# ethernet-wing-v1_00.net
KiCad netlist of a schematic drawn in EAGLE
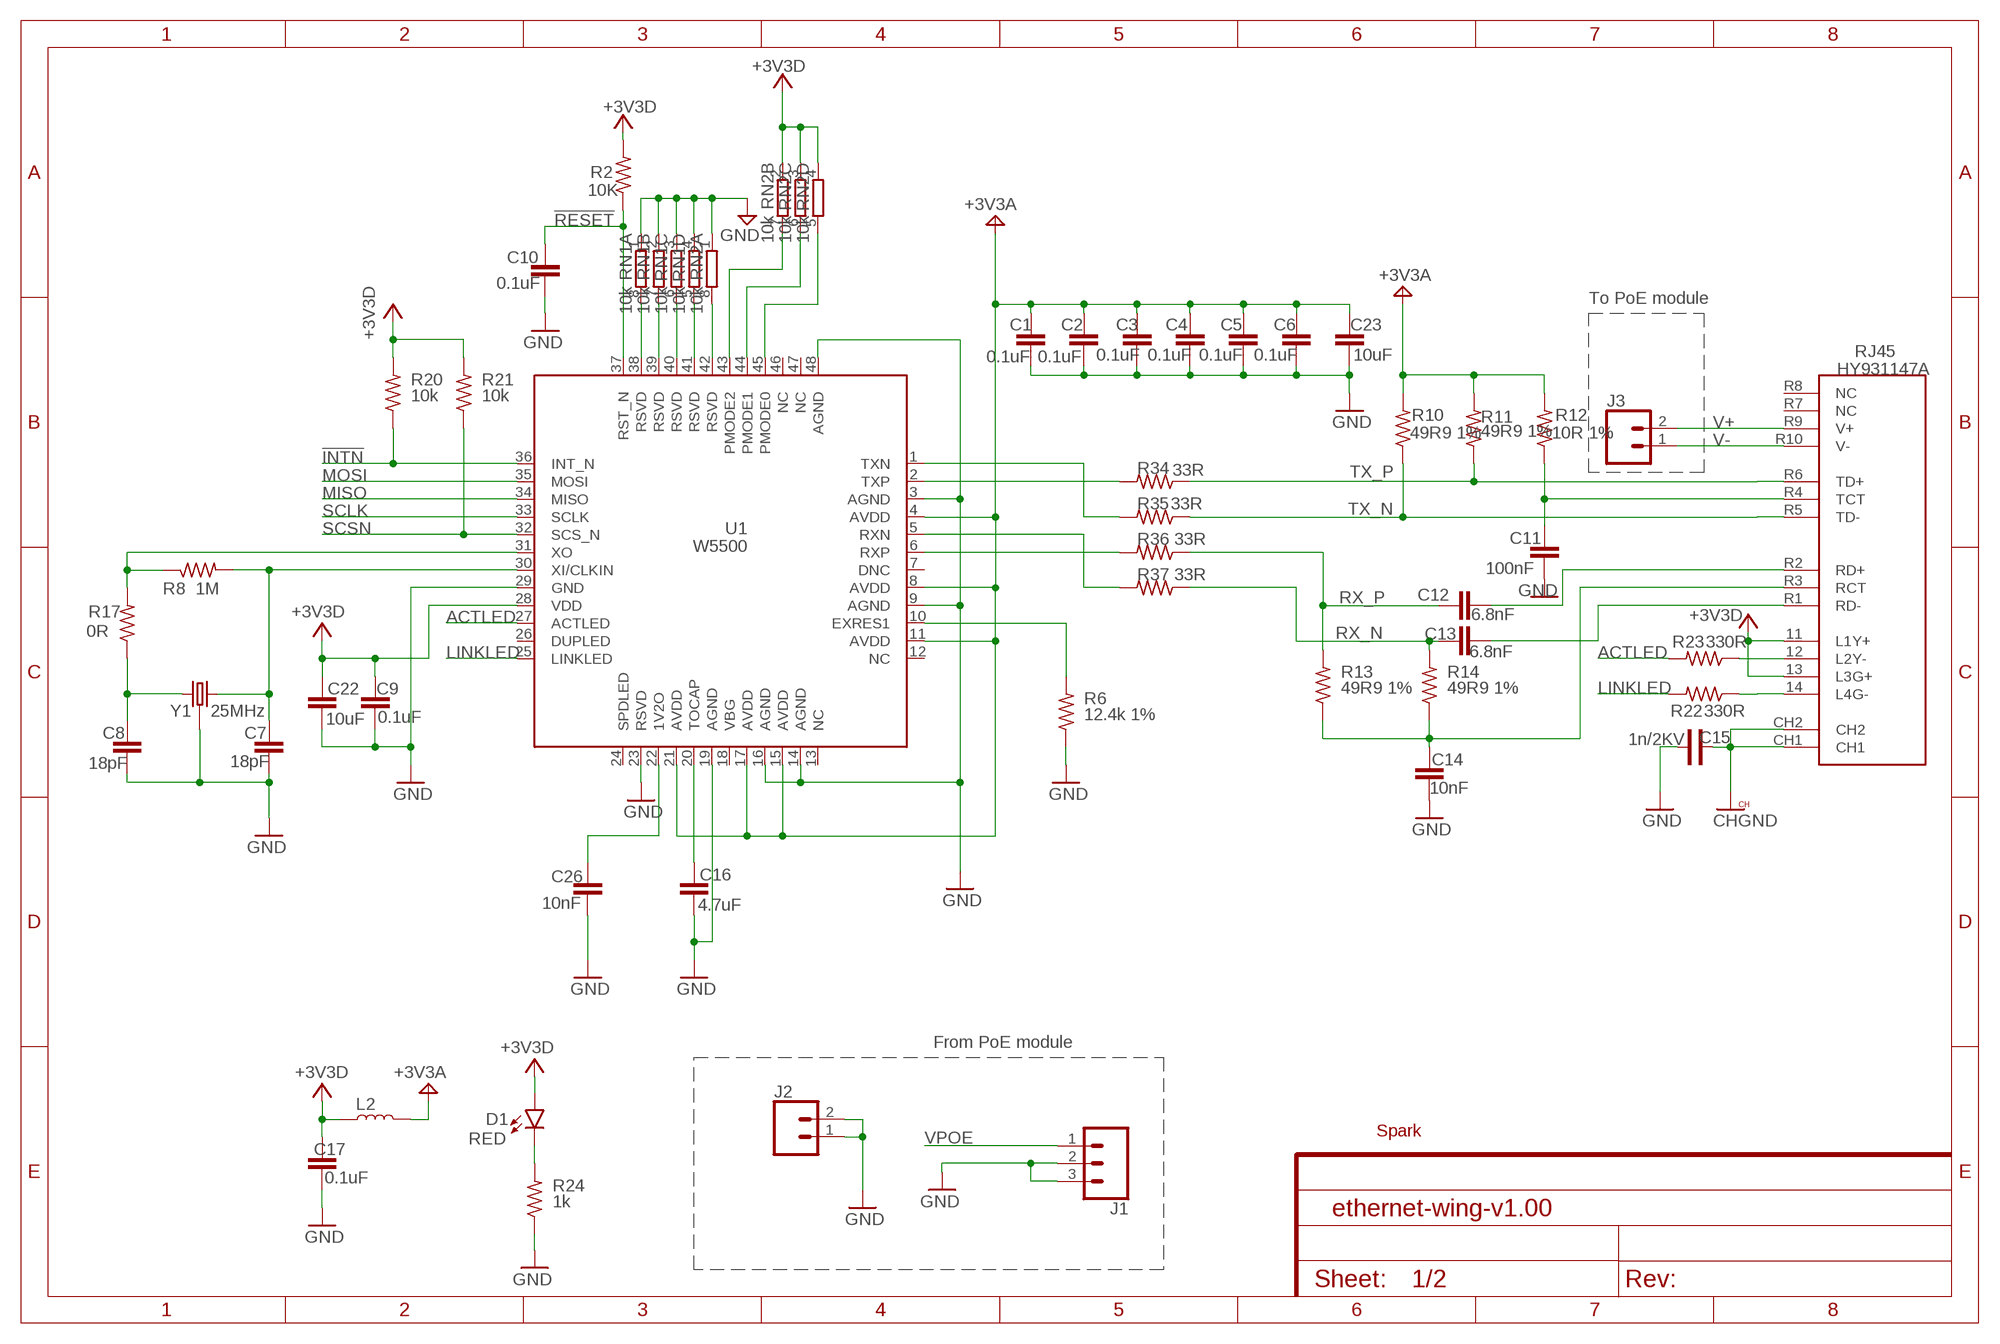
[diagram p0: schematic, sheet 1]
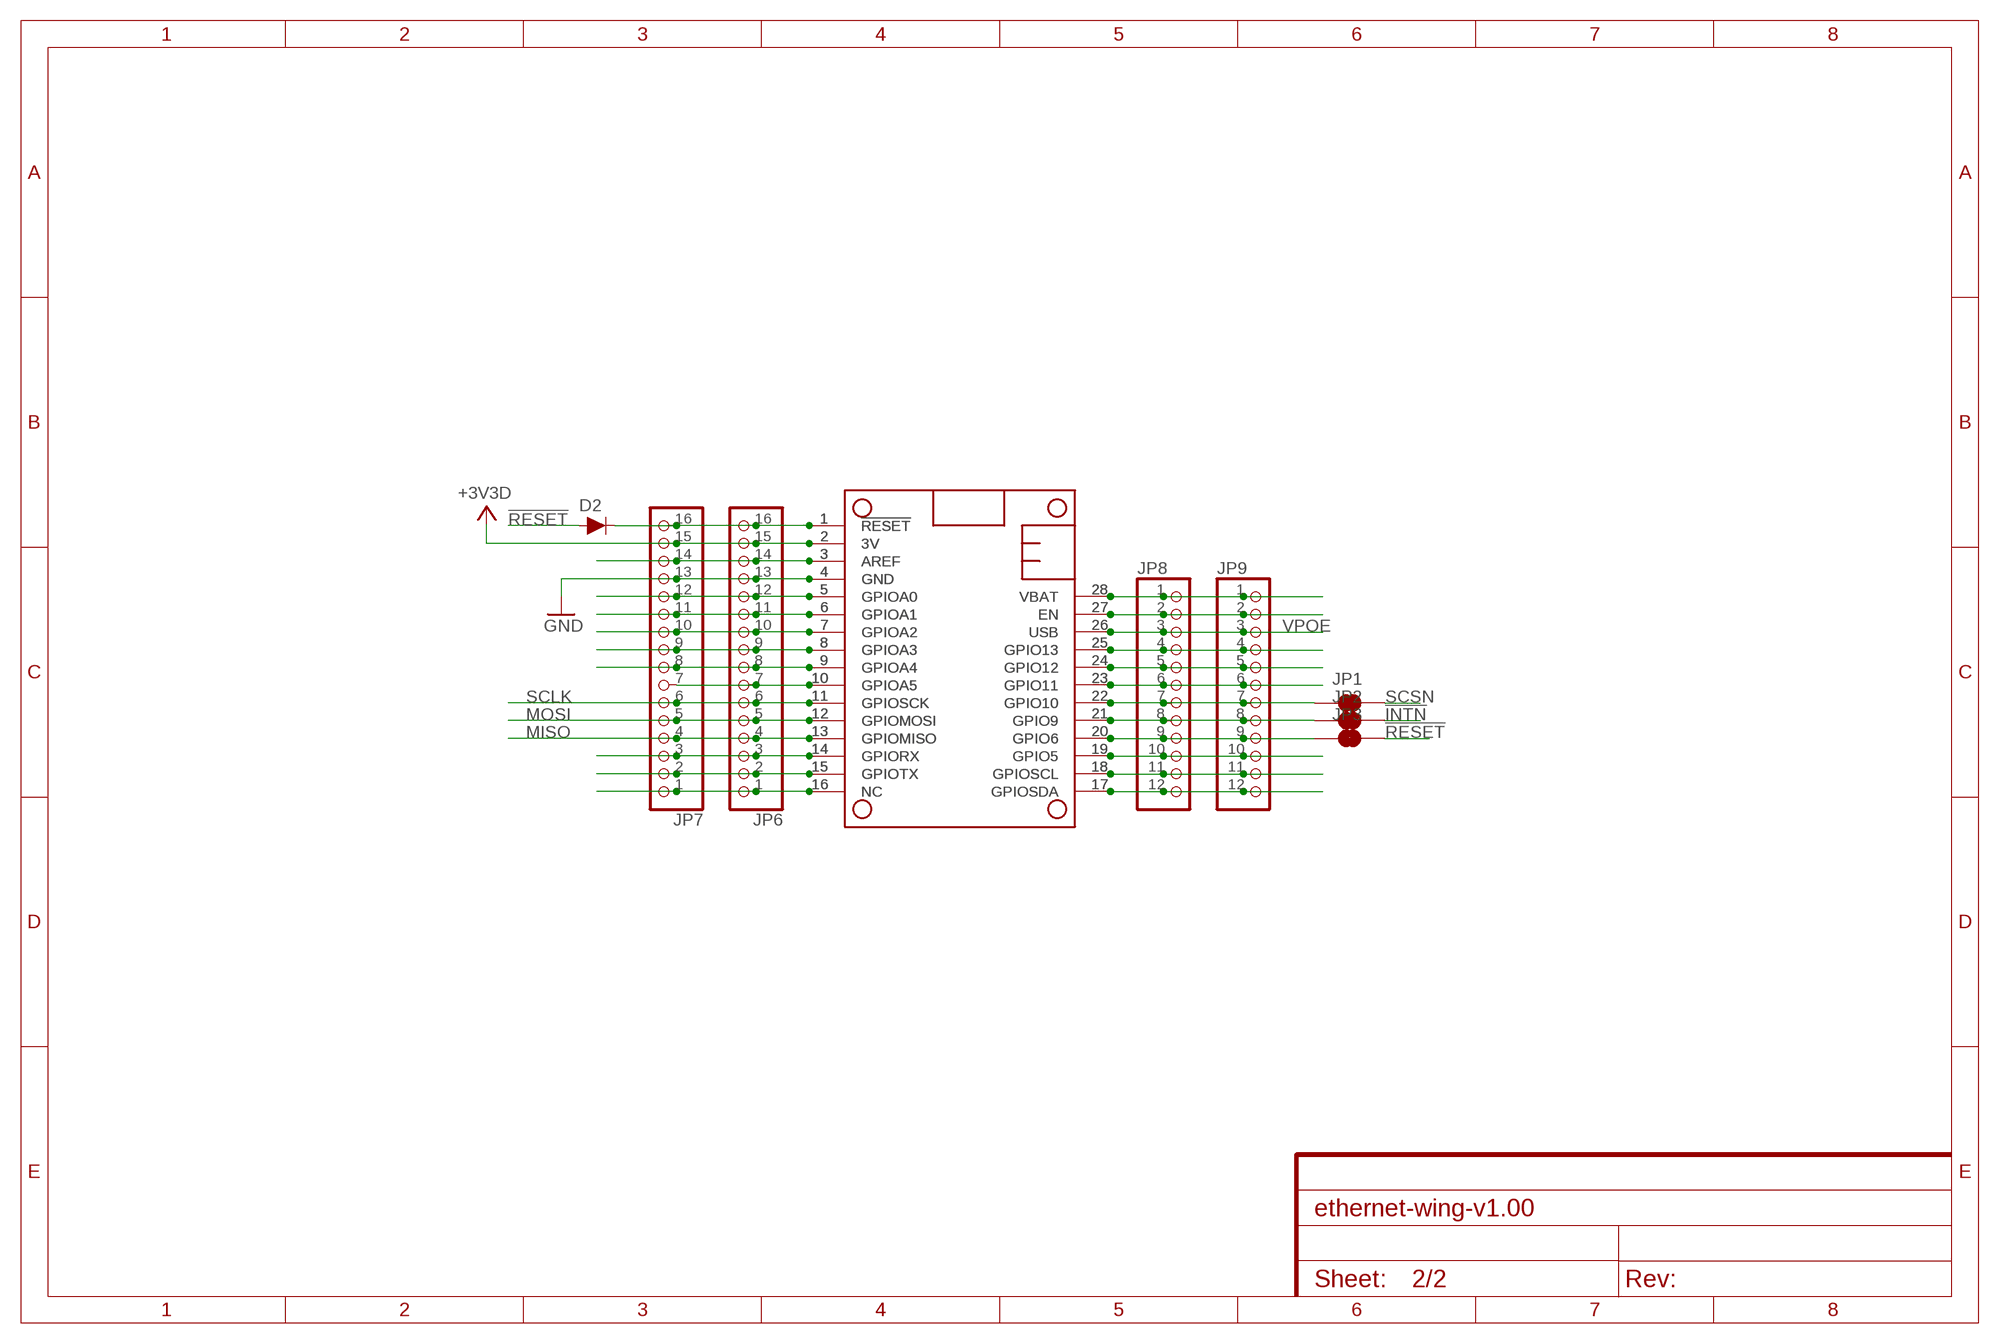
[diagram p1: schematic, sheet 2]

(export (version "E")
  (design (tool "Eeschema 10.0.6"))
  (components
    (comp (ref "C1")
      (value "0.1uF")
      (footprint "eagle-import:C0402_B")
      (libsource (lib "eagle-import") (part "CAP_1"))
    )
    (comp (ref "C2")
      (value "0.1uF")
      (footprint "eagle-import:C0402_B")
      (libsource (lib "eagle-import") (part "CAP_1"))
    )
    (comp (ref "C3")
      (value "0.1uF")
      (footprint "eagle-import:C0402_B")
      (libsource (lib "eagle-import") (part "CAP_1"))
    )
    (comp (ref "C4")
      (value "0.1uF")
      (footprint "eagle-import:C0402_B")
      (libsource (lib "eagle-import") (part "CAP_1"))
    )
    (comp (ref "C5")
      (value "0.1uF")
      (footprint "eagle-import:C0402_B")
      (libsource (lib "eagle-import") (part "CAP_1"))
    )
    (comp (ref "C6")
      (value "0.1uF")
      (footprint "eagle-import:C0402_B")
      (libsource (lib "eagle-import") (part "CAP_1"))
    )
    (comp (ref "C7")
      (value "18pF")
      (footprint "eagle-import:C0402_B")
      (libsource (lib "eagle-import") (part "CAP_1"))
    )
    (comp (ref "C8")
      (value "18pF")
      (footprint "eagle-import:C0402_B")
      (libsource (lib "eagle-import") (part "CAP_1"))
    )
    (comp (ref "C9")
      (value "0.1uF")
      (footprint "eagle-import:C0402_B")
      (libsource (lib "eagle-import") (part "CAP_1"))
    )
    (comp (ref "C10")
      (value "0.1uF")
      (footprint "eagle-import:C0402_B")
      (libsource (lib "eagle-import") (part "CAP_1"))
    )
    (comp (ref "C11")
      (value "100nF")
      (footprint "eagle-import:C0402_B")
      (libsource (lib "eagle-import") (part "CAP_1"))
    )
    (comp (ref "C12")
      (value "6.8nF")
      (footprint "eagle-import:C0402_B")
      (libsource (lib "eagle-import") (part "CAP_1"))
    )
    (comp (ref "C13")
      (value "6.8nF")
      (footprint "eagle-import:C0402_B")
      (libsource (lib "eagle-import") (part "CAP_1"))
    )
    (comp (ref "C14")
      (value "10nF")
      (footprint "eagle-import:C0402_B")
      (libsource (lib "eagle-import") (part "CAP_1"))
    )
    (comp (ref "C15")
      (value "1n/2KV")
      (footprint "eagle-import:C-1808")
      (libsource (lib "eagle-import") (part "C-1808"))
    )
    (comp (ref "C16")
      (value "4.7uF")
      (footprint "eagle-import:0603")
      (libsource (lib "eagle-import") (part "0.18UF-0603-10V-10%"))
    )
    (comp (ref "C17")
      (value "0.1uF")
      (footprint "eagle-import:C0402_B")
      (libsource (lib "eagle-import") (part "CAP_1"))
    )
    (comp (ref "C22")
      (value "10uF")
      (footprint "eagle-import:0603")
      (libsource (lib "eagle-import") (part "0.18UF-0603-10V-10%"))
    )
    (comp (ref "C23")
      (value "10uF")
      (footprint "eagle-import:0603")
      (libsource (lib "eagle-import") (part "0.18UF-0603-10V-10%"))
    )
    (comp (ref "C26")
      (value "10nF")
      (footprint "eagle-import:C0402_B")
      (libsource (lib "eagle-import") (part "CAP_1"))
    )
    (comp (ref "D1")
      (value "RED")
      (footprint "eagle-import:LED-0603")
      (libsource (lib "eagle-import") (part "LED-RED0603"))
    )
    (comp (ref "J1")
      (value "CONN_03")
      (footprint "eagle-import:1X03")
      (libsource (lib "eagle-import") (part "CONN_03"))
    )
    (comp (ref "J2")
      (value "CONN_02")
      (footprint "eagle-import:1X02")
      (libsource (lib "eagle-import") (part "CONN_02"))
    )
    (comp (ref "J3")
      (value "CONN_02")
      (footprint "eagle-import:1X02")
      (libsource (lib "eagle-import") (part "CONN_02"))
    )
    (comp (ref "L2")
      (value "INDUCTOR-0805-3.3UH")
      (footprint "eagle-import:0805")
      (libsource (lib "eagle-import") (part "INDUCTOR-0805-3.3UH"))
    )
    (comp (ref "R2")
      (value "10K")
      (footprint "eagle-import:R0402_B")
      (libsource (lib "eagle-import") (part "R-US_"))
    )
    (comp (ref "R6")
      (value "12.4k 1%")
      (footprint "eagle-import:R0402_B")
      (libsource (lib "eagle-import") (part "R-US_"))
    )
    (comp (ref "R8")
      (value "1M")
      (footprint "eagle-import:R0402_B")
      (libsource (lib "eagle-import") (part "R-US_"))
    )
    (comp (ref "R10")
      (value "49R9 1%")
      (footprint "eagle-import:R0402_B")
      (libsource (lib "eagle-import") (part "R-US_"))
    )
    (comp (ref "R11")
      (value "49R9 1%")
      (footprint "eagle-import:R0402_B")
      (libsource (lib "eagle-import") (part "R-US_"))
    )
    (comp (ref "R12")
      (value "10R 1%")
      (footprint "eagle-import:R0402_B")
      (libsource (lib "eagle-import") (part "R-US_"))
    )
    (comp (ref "R13")
      (value "49R9 1%")
      (footprint "eagle-import:R0402_B")
      (libsource (lib "eagle-import") (part "R-US_"))
    )
    (comp (ref "R14")
      (value "49R9 1%")
      (footprint "eagle-import:R0402_B")
      (libsource (lib "eagle-import") (part "R-US_"))
    )
    (comp (ref "R17")
      (value "0R")
      (footprint "eagle-import:R0402_B")
      (libsource (lib "eagle-import") (part "R-US_"))
    )
    (comp (ref "R20")
      (value "10k")
      (footprint "eagle-import:R0402_B")
      (libsource (lib "eagle-import") (part "R-US_"))
    )
    (comp (ref "R21")
      (value "10k")
      (footprint "eagle-import:R0402_B")
      (libsource (lib "eagle-import") (part "R-US_"))
    )
    (comp (ref "R22")
      (value "330R")
      (footprint "eagle-import:R0402_B")
      (libsource (lib "eagle-import") (part "R-US_"))
    )
    (comp (ref "R23")
      (value "330R")
      (footprint "eagle-import:R0402_B")
      (libsource (lib "eagle-import") (part "R-US_"))
    )
    (comp (ref "R24")
      (value "1k")
      (footprint "eagle-import:R0402_B")
      (libsource (lib "eagle-import") (part "R-US_"))
    )
    (comp (ref "R34")
      (value "33R")
      (footprint "eagle-import:R0402_B")
      (libsource (lib "eagle-import") (part "R-US_"))
    )
    (comp (ref "R35")
      (value "33R")
      (footprint "eagle-import:R0402_B")
      (libsource (lib "eagle-import") (part "R-US_"))
    )
    (comp (ref "R36")
      (value "33R")
      (footprint "eagle-import:R0402_B")
      (libsource (lib "eagle-import") (part "R-US_"))
    )
    (comp (ref "R37")
      (value "33R")
      (footprint "eagle-import:R0402_B")
      (libsource (lib "eagle-import") (part "R-US_"))
    )
    (comp (ref "RJ45")
      (value "HY931147A")
      (footprint "eagle-import:ARDUINO-ETHERNET-SHIELD2-V2_CONNETTORI_POE-RJ45")
      (libsource (lib "eagle-import") (part "ARDUINO-ETHERNET-SHIELD2-V2_POE_RJ45"))
    )
    (comp (ref "RN1")
      (value "10k")
      (footprint "eagle-import:4X0402ARV341")
      (libsource (lib "eagle-import") (part "4R-N0402ARV341"))
    )
    (comp (ref "RN2")
      (value "10k")
      (footprint "eagle-import:4X0402ARV341")
      (libsource (lib "eagle-import") (part "4R-N0402ARV341"))
    )
    (comp (ref "U$2")
      (value "SPARK_LOGO2")
      (footprint "eagle-import:SPARK_LOGO2")
      (libsource (lib "eagle-import") (part "SPARK_LOGO2"))
    )
    (comp (ref "U1")
      (value "W5500")
      (footprint "eagle-import:W5500")
      (libsource (lib "eagle-import") (part "W5500"))
    )
    (comp (ref "Y1")
      (value "25MHz")
      (footprint "eagle-import:CRYSTAL-SMD-3.2X2.5MM")
      (libsource (lib "eagle-import") (part "CRYSTAL-GROUNDEDSMD-3.2X2.5"))
    )
    (comp (ref "D2")
      (value "DIODE-BAS16J")
      (footprint "eagle-import:SOD-323")
      (libsource (lib "eagle-import") (part "DIODE-BAS16J"))
    )
    (comp (ref "JP1")
      (value "JUMPER-SMT_2_NC_TRACE_NO-SILK")
      (footprint "eagle-import:SMT-JUMPER_2_NC_TRACE_NO-SILK")
      (libsource (lib "eagle-import") (part "JUMPER-SMT_2_NC_TRACE_NO-SILK"))
    )
    (comp (ref "JP2")
      (value "JUMPER-SMT_2_NC_TRACE_NO-SILK")
      (footprint "eagle-import:SMT-JUMPER_2_NC_TRACE_NO-SILK")
      (libsource (lib "eagle-import") (part "JUMPER-SMT_2_NC_TRACE_NO-SILK"))
    )
    (comp (ref "JP3")
      (value "JUMPER-SMT_2_NC_TRACE_NO-SILK")
      (footprint "eagle-import:SMT-JUMPER_2_NC_TRACE_NO-SILK")
      (libsource (lib "eagle-import") (part "JUMPER-SMT_2_NC_TRACE_NO-SILK"))
    )
    (comp (ref "JP6")
      (value "MICROBUILDER_HEADER-1X16_76MIL")
      (footprint "eagle-import:MICROBUILDER_1X16_ROUND_76MIL")
      (libsource (lib "eagle-import") (part "MICROBUILDER_HEADER-1X16_76MIL"))
    )
    (comp (ref "JP7")
      (value "MICROBUILDER_HEADER-1X16_76MIL")
      (footprint "eagle-import:MICROBUILDER_1X16_ROUND_76MIL")
      (libsource (lib "eagle-import") (part "MICROBUILDER_HEADER-1X16_76MIL"))
    )
    (comp (ref "JP8")
      (value "MICROBUILDER_HEADER-1X1276MIL")
      (footprint "eagle-import:MICROBUILDER_1X12_ROUND_76MIL")
      (libsource (lib "eagle-import") (part "MICROBUILDER_HEADER-1X1276MIL"))
    )
    (comp (ref "JP9")
      (value "MICROBUILDER_HEADER-1X1276MIL")
      (footprint "eagle-import:MICROBUILDER_1X12_ROUND_76MIL")
      (libsource (lib "eagle-import") (part "MICROBUILDER_HEADER-1X1276MIL"))
    )
    (comp (ref "MS1")
      (value "MICROBUILDER_FEATHERWING_NODIM")
      (footprint "eagle-import:MICROBUILDER_FEATHERWING_DIM")
      (libsource (lib "eagle-import") (part "MICROBUILDER_FEATHERWING_NODIM"))
    )
    (comp (ref "MS2")
      (value "MICROBUILDER_FEATHERWING_NODIM")
      (footprint "eagle-import:MICROBUILDER_FEATHERWING_DIM")
      (libsource (lib "eagle-import") (part "MICROBUILDER_FEATHERWING_NODIM"))
    )
  )
  (nets
    (net (code "1") (name "+3V3") (class "Default")
      (node (ref "C17") (pin "2") (pinfunction "P$2_2") (pintype "passive"))
      (node (ref "C22") (pin "1") (pinfunction "1_1") (pintype "passive"))
      (node (ref "C9") (pin "2") (pinfunction "P$2_2") (pintype "passive"))
      (node (ref "D1") (pin "A") (pinfunction "A_A") (pintype "passive"))
      (node (ref "JP6") (pin "15") (pinfunction "15_15") (pintype "passive"))
      (node (ref "JP7") (pin "15") (pinfunction "15_15") (pintype "passive"))
      (node (ref "L2") (pin "1") (pinfunction "1_1") (pintype "passive"))
      (node (ref "MS1") (pin "2") (pinfunction "3V_2") (pintype "power_in"))
      (node (ref "MS2") (pin "2") (pinfunction "3V_2") (pintype "power_in"))
      (node (ref "R2") (pin "2") (pinfunction "2_2") (pintype "passive"))
      (node (ref "R20") (pin "2") (pinfunction "2_2") (pintype "passive"))
      (node (ref "R21") (pin "2") (pinfunction "2_2") (pintype "passive"))
      (node (ref "RJ45") (pin "11") (pinfunction "L1Y+_11") (pintype "bidirectional"))
      (node (ref "RJ45") (pin "13") (pinfunction "L3G+_13") (pintype "bidirectional"))
      (node (ref "RN2") (pin "2") (pinfunction "1_2") (pintype "passive"))
      (node (ref "RN2") (pin "3") (pinfunction "1_3") (pintype "passive"))
      (node (ref "RN2") (pin "4") (pinfunction "1_4") (pintype "passive"))
      (node (ref "U1") (pin "28") (pinfunction "VDD_28") (pintype "passive"))
    )
    (net (code "2") (name "+3V3A") (class "Default")
      (node (ref "C1") (pin "2") (pinfunction "P$2_2") (pintype "passive"))
      (node (ref "C2") (pin "2") (pinfunction "P$2_2") (pintype "passive"))
      (node (ref "C23") (pin "1") (pinfunction "1_1") (pintype "passive"))
      (node (ref "C3") (pin "2") (pinfunction "P$2_2") (pintype "passive"))
      (node (ref "C4") (pin "2") (pinfunction "P$2_2") (pintype "passive"))
      (node (ref "C5") (pin "2") (pinfunction "P$2_2") (pintype "passive"))
      (node (ref "C6") (pin "2") (pinfunction "P$2_2") (pintype "passive"))
      (node (ref "L2") (pin "2") (pinfunction "2_2") (pintype "passive"))
      (node (ref "R10") (pin "2") (pinfunction "2_2") (pintype "passive"))
      (node (ref "R11") (pin "2") (pinfunction "2_2") (pintype "passive"))
      (node (ref "R12") (pin "2") (pinfunction "2_2") (pintype "passive"))
      (node (ref "U1") (pin "11") (pinfunction "AVDD_11") (pintype "passive"))
      (node (ref "U1") (pin "15") (pinfunction "AVDD_15") (pintype "passive"))
      (node (ref "U1") (pin "17") (pinfunction "AVDD_17") (pintype "passive"))
      (node (ref "U1") (pin "21") (pinfunction "AVDD_21") (pintype "passive"))
      (node (ref "U1") (pin "4") (pinfunction "AVDD_4") (pintype "passive"))
      (node (ref "U1") (pin "8") (pinfunction "AVDD_8") (pintype "passive"))
    )
    (net (code "3") (name "ACTLED") (class "Default")
      (node (ref "R23") (pin "2") (pinfunction "2_2") (pintype "passive"))
      (node (ref "U1") (pin "27") (pinfunction "ACTLED_27") (pintype "passive"))
    )
    (net (code "4") (name "CHGND") (class "Default")
      (node (ref "C15") (pin "P$1") (pinfunction "P$1_P$1") (pintype "passive"))
      (node (ref "RJ45") (pin "CH1") (pinfunction "CH1_CH1") (pintype "bidirectional"))
      (node (ref "RJ45") (pin "CH2") (pinfunction "CH2_CH2") (pintype "bidirectional"))
    )
    (net (code "5") (name "GND") (class "Default")
      (node (ref "C1") (pin "1") (pinfunction "P$1_1") (pintype "passive"))
      (node (ref "C10") (pin "1") (pinfunction "P$1_1") (pintype "passive"))
      (node (ref "C11") (pin "1") (pinfunction "P$1_1") (pintype "passive"))
      (node (ref "C14") (pin "1") (pinfunction "P$1_1") (pintype "passive"))
      (node (ref "C15") (pin "P$2") (pinfunction "P$2_P$2") (pintype "passive"))
      (node (ref "C16") (pin "2") (pinfunction "2_2") (pintype "passive"))
      (node (ref "C17") (pin "1") (pinfunction "P$1_1") (pintype "passive"))
      (node (ref "C2") (pin "1") (pinfunction "P$1_1") (pintype "passive"))
      (node (ref "C22") (pin "2") (pinfunction "2_2") (pintype "passive"))
      (node (ref "C23") (pin "2") (pinfunction "2_2") (pintype "passive"))
      (node (ref "C26") (pin "1") (pinfunction "P$1_1") (pintype "passive"))
      (node (ref "C3") (pin "1") (pinfunction "P$1_1") (pintype "passive"))
      (node (ref "C4") (pin "1") (pinfunction "P$1_1") (pintype "passive"))
      (node (ref "C5") (pin "1") (pinfunction "P$1_1") (pintype "passive"))
      (node (ref "C6") (pin "1") (pinfunction "P$1_1") (pintype "passive"))
      (node (ref "C7") (pin "1") (pinfunction "P$1_1") (pintype "passive"))
      (node (ref "C8") (pin "1") (pinfunction "P$1_1") (pintype "passive"))
      (node (ref "C9") (pin "1") (pinfunction "P$1_1") (pintype "passive"))
      (node (ref "J1") (pin "2") (pinfunction "2_2") (pintype "passive"))
      (node (ref "J1") (pin "3") (pinfunction "3_3") (pintype "passive"))
      (node (ref "J2") (pin "1") (pinfunction "1_1") (pintype "passive"))
      (node (ref "J2") (pin "2") (pinfunction "2_2") (pintype "passive"))
      (node (ref "JP6") (pin "13") (pinfunction "13_13") (pintype "passive"))
      (node (ref "JP7") (pin "13") (pinfunction "13_13") (pintype "passive"))
      (node (ref "MS1") (pin "4") (pinfunction "GND_4") (pintype "power_in"))
      (node (ref "MS2") (pin "4") (pinfunction "GND_4") (pintype "power_in"))
      (node (ref "R24") (pin "1") (pinfunction "1_1") (pintype "passive"))
      (node (ref "R6") (pin "1") (pinfunction "1_1") (pintype "passive"))
      (node (ref "RN1") (pin "1") (pinfunction "1_1") (pintype "passive"))
      (node (ref "RN1") (pin "2") (pinfunction "1_2") (pintype "passive"))
      (node (ref "RN1") (pin "3") (pinfunction "1_3") (pintype "passive"))
      (node (ref "RN1") (pin "4") (pinfunction "1_4") (pintype "passive"))
      (node (ref "RN2") (pin "1") (pinfunction "1_1") (pintype "passive"))
      (node (ref "U1") (pin "14") (pinfunction "AGND_14") (pintype "passive"))
      (node (ref "U1") (pin "16") (pinfunction "AGND_16") (pintype "passive"))
      (node (ref "U1") (pin "19") (pinfunction "AGND_19") (pintype "passive"))
      (node (ref "U1") (pin "23") (pinfunction "RSVD_23") (pintype "passive"))
      (node (ref "U1") (pin "29") (pinfunction "GND_29") (pintype "passive"))
      (node (ref "U1") (pin "3") (pinfunction "AGND_3") (pintype "passive"))
      (node (ref "U1") (pin "48") (pinfunction "AGND_48") (pintype "passive"))
      (node (ref "U1") (pin "9") (pinfunction "AGND_9") (pintype "passive"))
      (node (ref "Y1") (pin "2") (pinfunction "3_2") (pintype "passive"))
      (node (ref "Y1") (pin "4") (pinfunction "3_4") (pintype "passive"))
    )
    (net (code "6") (name "LINKLED") (class "Default")
      (node (ref "R22") (pin "2") (pinfunction "2_2") (pintype "passive"))
      (node (ref "U1") (pin "25") (pinfunction "LINKLED_25") (pintype "passive"))
    )
    (net (code "7") (name "MISO") (class "Default")
      (node (ref "JP6") (pin "4") (pinfunction "4_4") (pintype "passive"))
      (node (ref "JP7") (pin "4") (pinfunction "4_4") (pintype "passive"))
      (node (ref "MS1") (pin "13") (pinfunction "GPIOMISO_13") (pintype "bidirectional"))
      (node (ref "MS2") (pin "13") (pinfunction "GPIOMISO_13") (pintype "bidirectional"))
      (node (ref "U1") (pin "34") (pinfunction "MISO_34") (pintype "passive"))
    )
    (net (code "8") (name "MOSI") (class "Default")
      (node (ref "JP6") (pin "5") (pinfunction "5_5") (pintype "passive"))
      (node (ref "JP7") (pin "5") (pinfunction "5_5") (pintype "passive"))
      (node (ref "MS1") (pin "12") (pinfunction "GPIOMOSI_12") (pintype "bidirectional"))
      (node (ref "MS2") (pin "12") (pinfunction "GPIOMOSI_12") (pintype "bidirectional"))
      (node (ref "U1") (pin "35") (pinfunction "MOSI_35") (pintype "passive"))
    )
    (net (code "9") (name "Net-(C7-P$2)") (class "Default")
      (node (ref "C7") (pin "2") (pinfunction "P$2_2") (pintype "passive"))
      (node (ref "R8") (pin "2") (pinfunction "2_2") (pintype "passive"))
      (node (ref "U1") (pin "30") (pinfunction "XI/CLKIN_30") (pintype "passive"))
      (node (ref "Y1") (pin "3") (pinfunction "2_3") (pintype "passive"))
    )
    (net (code "10") (name "Net-(C8-P$2)") (class "Default")
      (node (ref "C8") (pin "2") (pinfunction "P$2_2") (pintype "passive"))
      (node (ref "R17") (pin "1") (pinfunction "1_1") (pintype "passive"))
      (node (ref "Y1") (pin "1") (pinfunction "1_1") (pintype "passive"))
    )
    (net (code "11") (name "Net-(C11-P$2)") (class "Default")
      (node (ref "C11") (pin "2") (pinfunction "P$2_2") (pintype "passive"))
      (node (ref "R12") (pin "1") (pinfunction "1_1") (pintype "passive"))
      (node (ref "RJ45") (pin "R4") (pinfunction "TCT_R4") (pintype "bidirectional"))
    )
    (net (code "12") (name "Net-(C12-P$2)") (class "Default")
      (node (ref "C12") (pin "2") (pinfunction "P$2_2") (pintype "passive"))
      (node (ref "RJ45") (pin "R2") (pinfunction "RD+_R2") (pintype "bidirectional"))
    )
    (net (code "13") (name "Net-(C13-P$2)") (class "Default")
      (node (ref "C13") (pin "2") (pinfunction "P$2_2") (pintype "passive"))
      (node (ref "RJ45") (pin "R1") (pinfunction "RD-_R1") (pintype "bidirectional"))
    )
    (net (code "14") (name "Net-(C14-P$2)") (class "Default")
      (node (ref "C14") (pin "2") (pinfunction "P$2_2") (pintype "passive"))
      (node (ref "R13") (pin "1") (pinfunction "1_1") (pintype "passive"))
      (node (ref "R14") (pin "1") (pinfunction "1_1") (pintype "passive"))
      (node (ref "RJ45") (pin "R3") (pinfunction "RCT_R3") (pintype "bidirectional"))
    )
    (net (code "15") (name "Net-(C26-P$2)") (class "Default")
      (node (ref "C26") (pin "2") (pinfunction "P$2_2") (pintype "passive"))
      (node (ref "U1") (pin "22") (pinfunction "1V2O_22") (pintype "passive"))
    )
    (net (code "16") (name "Net-(D1-PadC)") (class "Default")
      (node (ref "D1") (pin "C") (pinfunction "C_C") (pintype "passive"))
      (node (ref "R24") (pin "2") (pinfunction "2_2") (pintype "passive"))
    )
    (net (code "17") (name "Net-(MS1-AREF)") (class "Default")
      (node (ref "JP6") (pin "14") (pinfunction "14_14") (pintype "passive"))
      (node (ref "JP7") (pin "14") (pinfunction "14_14") (pintype "passive"))
      (node (ref "MS1") (pin "3") (pinfunction "AREF_3") (pintype "passive"))
      (node (ref "MS2") (pin "3") (pinfunction "AREF_3") (pintype "passive"))
    )
    (net (code "18") (name "Net-(MS1-EN)") (class "Default")
      (node (ref "JP8") (pin "2") (pinfunction "2_2") (pintype "passive"))
      (node (ref "JP9") (pin "2") (pinfunction "2_2") (pintype "passive"))
      (node (ref "MS1") (pin "27") (pinfunction "EN_27") (pintype "passive"))
      (node (ref "MS2") (pin "27") (pinfunction "EN_27") (pintype "passive"))
    )
    (net (code "19") (name "Net-(MS1-GPIO5)") (class "Default")
      (node (ref "JP8") (pin "10") (pinfunction "10_10") (pintype "passive"))
      (node (ref "JP9") (pin "10") (pinfunction "10_10") (pintype "passive"))
      (node (ref "MS1") (pin "19") (pinfunction "GPIO5_19") (pintype "bidirectional"))
      (node (ref "MS2") (pin "19") (pinfunction "GPIO5_19") (pintype "bidirectional"))
    )
    (net (code "20") (name "Net-(MS1-GPIO6)") (class "Default")
      (node (ref "JP3") (pin "1") (pinfunction "1_1") (pintype "passive"))
      (node (ref "JP8") (pin "9") (pinfunction "9_9") (pintype "passive"))
      (node (ref "JP9") (pin "9") (pinfunction "9_9") (pintype "passive"))
      (node (ref "MS1") (pin "20") (pinfunction "GPIO6_20") (pintype "bidirectional"))
      (node (ref "MS2") (pin "20") (pinfunction "GPIO6_20") (pintype "bidirectional"))
    )
    (net (code "21") (name "Net-(MS1-GPIO9)") (class "Default")
      (node (ref "JP2") (pin "1") (pinfunction "1_1") (pintype "passive"))
      (node (ref "JP8") (pin "8") (pinfunction "8_8") (pintype "passive"))
      (node (ref "JP9") (pin "8") (pinfunction "8_8") (pintype "passive"))
      (node (ref "MS1") (pin "21") (pinfunction "GPIO9_21") (pintype "bidirectional"))
      (node (ref "MS2") (pin "21") (pinfunction "GPIO9_21") (pintype "bidirectional"))
    )
    (net (code "22") (name "Net-(MS1-GPIO10)") (class "Default")
      (node (ref "JP1") (pin "1") (pinfunction "1_1") (pintype "passive"))
      (node (ref "JP8") (pin "7") (pinfunction "7_7") (pintype "passive"))
      (node (ref "JP9") (pin "7") (pinfunction "7_7") (pintype "passive"))
      (node (ref "MS1") (pin "22") (pinfunction "GPIO10_22") (pintype "bidirectional"))
      (node (ref "MS2") (pin "22") (pinfunction "GPIO10_22") (pintype "bidirectional"))
    )
    (net (code "23") (name "Net-(MS1-GPIO11)") (class "Default")
      (node (ref "JP8") (pin "6") (pinfunction "6_6") (pintype "passive"))
      (node (ref "JP9") (pin "6") (pinfunction "6_6") (pintype "passive"))
      (node (ref "MS1") (pin "23") (pinfunction "GPIO11_23") (pintype "bidirectional"))
      (node (ref "MS2") (pin "23") (pinfunction "GPIO11_23") (pintype "bidirectional"))
    )
    (net (code "24") (name "Net-(MS1-GPIO12)") (class "Default")
      (node (ref "JP8") (pin "5") (pinfunction "5_5") (pintype "passive"))
      (node (ref "JP9") (pin "5") (pinfunction "5_5") (pintype "passive"))
      (node (ref "MS1") (pin "24") (pinfunction "GPIO12_24") (pintype "bidirectional"))
      (node (ref "MS2") (pin "24") (pinfunction "GPIO12_24") (pintype "bidirectional"))
    )
    (net (code "25") (name "Net-(MS1-GPIO13)") (class "Default")
      (node (ref "JP8") (pin "4") (pinfunction "4_4") (pintype "passive"))
      (node (ref "JP9") (pin "4") (pinfunction "4_4") (pintype "passive"))
      (node (ref "MS1") (pin "25") (pinfunction "GPIO13_25") (pintype "bidirectional"))
      (node (ref "MS2") (pin "25") (pinfunction "GPIO13_25") (pintype "bidirectional"))
    )
    (net (code "26") (name "Net-(MS1-GPIOA0)") (class "Default")
      (node (ref "JP6") (pin "12") (pinfunction "12_12") (pintype "passive"))
      (node (ref "JP7") (pin "12") (pinfunction "12_12") (pintype "passive"))
      (node (ref "MS1") (pin "5") (pinfunction "GPIOA0_5") (pintype "bidirectional"))
      (node (ref "MS2") (pin "5") (pinfunction "GPIOA0_5") (pintype "bidirectional"))
    )
    (net (code "27") (name "Net-(MS1-GPIOA1)") (class "Default")
      (node (ref "JP6") (pin "11") (pinfunction "11_11") (pintype "passive"))
      (node (ref "JP7") (pin "11") (pinfunction "11_11") (pintype "passive"))
      (node (ref "MS1") (pin "6") (pinfunction "GPIOA1_6") (pintype "bidirectional"))
      (node (ref "MS2") (pin "6") (pinfunction "GPIOA1_6") (pintype "bidirectional"))
    )
    (net (code "28") (name "Net-(MS1-GPIOA2)") (class "Default")
      (node (ref "JP6") (pin "10") (pinfunction "10_10") (pintype "passive"))
      (node (ref "JP7") (pin "10") (pinfunction "10_10") (pintype "passive"))
      (node (ref "MS1") (pin "7") (pinfunction "GPIOA2_7") (pintype "bidirectional"))
      (node (ref "MS2") (pin "7") (pinfunction "GPIOA2_7") (pintype "bidirectional"))
    )
    (net (code "29") (name "Net-(MS1-GPIOA3)") (class "Default")
      (node (ref "JP6") (pin "9") (pinfunction "9_9") (pintype "passive"))
      (node (ref "JP7") (pin "9") (pinfunction "9_9") (pintype "passive"))
      (node (ref "MS1") (pin "8") (pinfunction "GPIOA3_8") (pintype "bidirectional"))
      (node (ref "MS2") (pin "8") (pinfunction "GPIOA3_8") (pintype "bidirectional"))
    )
    (net (code "30") (name "Net-(MS1-GPIOA4)") (class "Default")
      (node (ref "JP6") (pin "8") (pinfunction "8_8") (pintype "passive"))
      (node (ref "JP7") (pin "8") (pinfunction "8_8") (pintype "passive"))
      (node (ref "MS1") (pin "9") (pinfunction "GPIOA4_9") (pintype "bidirectional"))
      (node (ref "MS2") (pin "9") (pinfunction "GPIOA4_9") (pintype "bidirectional"))
    )
    (net (code "31") (name "Net-(MS1-GPIOA5)") (class "Default")
      (node (ref "JP6") (pin "7") (pinfunction "7_7") (pintype "passive"))
      (node (ref "JP7") (pin "7") (pinfunction "7_7") (pintype "passive"))
      (node (ref "MS1") (pin "10") (pinfunction "GPIOA5_10") (pintype "bidirectional"))
      (node (ref "MS2") (pin "10") (pinfunction "GPIOA5_10") (pintype "bidirectional"))
    )
    (net (code "32") (name "Net-(MS1-GPIORX)") (class "Default")
      (node (ref "JP6") (pin "3") (pinfunction "3_3") (pintype "passive"))
      (node (ref "JP7") (pin "3") (pinfunction "3_3") (pintype "passive"))
      (node (ref "MS1") (pin "14") (pinfunction "GPIORX_14") (pintype "bidirectional"))
      (node (ref "MS2") (pin "14") (pinfunction "GPIORX_14") (pintype "bidirectional"))
    )
    (net (code "33") (name "Net-(MS1-GPIOSCL)") (class "Default")
      (node (ref "JP8") (pin "11") (pinfunction "11_11") (pintype "passive"))
      (node (ref "JP9") (pin "11") (pinfunction "11_11") (pintype "passive"))
      (node (ref "MS1") (pin "18") (pinfunction "GPIOSCL_18") (pintype "bidirectional"))
      (node (ref "MS2") (pin "18") (pinfunction "GPIOSCL_18") (pintype "bidirectional"))
    )
    (net (code "34") (name "Net-(MS1-GPIOSDA)") (class "Default")
      (node (ref "JP8") (pin "12") (pinfunction "12_12") (pintype "passive"))
      (node (ref "JP9") (pin "12") (pinfunction "12_12") (pintype "passive"))
      (node (ref "MS1") (pin "17") (pinfunction "GPIOSDA_17") (pintype "bidirectional"))
      (node (ref "MS2") (pin "17") (pinfunction "GPIOSDA_17") (pintype "bidirectional"))
    )
    (net (code "35") (name "Net-(MS1-GPIOTX)") (class "Default")
      (node (ref "JP6") (pin "2") (pinfunction "2_2") (pintype "passive"))
      (node (ref "JP7") (pin "2") (pinfunction "2_2") (pintype "passive"))
      (node (ref "MS1") (pin "15") (pinfunction "GPIOTX_15") (pintype "bidirectional"))
      (node (ref "MS2") (pin "15") (pinfunction "GPIOTX_15") (pintype "bidirectional"))
    )
    (net (code "36") (name "Net-(MS1-NC)") (class "Default")
      (node (ref "JP6") (pin "1") (pinfunction "1_1") (pintype "passive"))
      (node (ref "JP7") (pin "1") (pinfunction "1_1") (pintype "passive"))
      (node (ref "MS1") (pin "16") (pinfunction "NC_16") (pintype "passive"))
      (node (ref "MS2") (pin "16") (pinfunction "NC_16") (pintype "passive"))
    )
    (net (code "37") (name "Net-(MS1-VBAT)") (class "Default")
      (node (ref "JP8") (pin "1") (pinfunction "1_1") (pintype "passive"))
      (node (ref "JP9") (pin "1") (pinfunction "1_1") (pintype "passive"))
      (node (ref "MS1") (pin "28") (pinfunction "VBAT_28") (pintype "power_in"))
      (node (ref "MS2") (pin "28") (pinfunction "VBAT_28") (pintype "power_in"))
    )
    (net (code "38") (name "Net-(MS1-~{RESET})") (class "Default")
      (node (ref "D2") (pin "C") (pinfunction "C_C") (pintype "passive"))
      (node (ref "JP6") (pin "16") (pinfunction "16_16") (pintype "passive"))
      (node (ref "JP7") (pin "16") (pinfunction "16_16") (pintype "passive"))
      (node (ref "MS1") (pin "1") (pinfunction "~{RESET}_1") (pintype "input"))
      (node (ref "MS2") (pin "1") (pinfunction "~{RESET}_1") (pintype "input"))
    )
    (net (code "39") (name "Net-(RJ45-L2Y-)") (class "Default")
      (node (ref "R23") (pin "1") (pinfunction "1_1") (pintype "passive"))
      (node (ref "RJ45") (pin "12") (pinfunction "L2Y-_12") (pintype "bidirectional"))
    )
    (net (code "40") (name "Net-(RJ45-L4G-)") (class "Default")
      (node (ref "R22") (pin "1") (pinfunction "1_1") (pintype "passive"))
      (node (ref "RJ45") (pin "14") (pinfunction "L4G-_14") (pintype "bidirectional"))
    )
    (net (code "41") (name "Net-(RN1A-2)") (class "Default")
      (node (ref "RN1") (pin "8") (pinfunction "2_8") (pintype "passive"))
      (node (ref "U1") (pin "38") (pinfunction "RSVD_38") (pintype "passive"))
    )
    (net (code "42") (name "Net-(RN1B-2)") (class "Default")
      (node (ref "RN1") (pin "7") (pinfunction "2_7") (pintype "passive"))
      (node (ref "U1") (pin "39") (pinfunction "RSVD_39") (pintype "passive"))
    )
    (net (code "43") (name "Net-(RN1C-2)") (class "Default")
      (node (ref "RN1") (pin "6") (pinfunction "2_6") (pintype "passive"))
      (node (ref "U1") (pin "40") (pinfunction "RSVD_40") (pintype "passive"))
    )
    (net (code "44") (name "Net-(RN1D-2)") (class "Default")
      (node (ref "RN1") (pin "5") (pinfunction "2_5") (pintype "passive"))
      (node (ref "U1") (pin "41") (pinfunction "RSVD_41") (pintype "passive"))
    )
    (net (code "45") (name "Net-(RN2A-2)") (class "Default")
      (node (ref "RN2") (pin "8") (pinfunction "2_8") (pintype "passive"))
      (node (ref "U1") (pin "42") (pinfunction "RSVD_42") (pintype "passive"))
    )
    (net (code "46") (name "Net-(RN2B-2)") (class "Default")
      (node (ref "RN2") (pin "7") (pinfunction "2_7") (pintype "passive"))
      (node (ref "U1") (pin "43") (pinfunction "PMODE2_43") (pintype "passive"))
    )
    (net (code "47") (name "Net-(RN2C-2)") (class "Default")
      (node (ref "RN2") (pin "6") (pinfunction "2_6") (pintype "passive"))
      (node (ref "U1") (pin "44") (pinfunction "PMODE1_44") (pintype "passive"))
    )
    (net (code "48") (name "Net-(RN2D-2)") (class "Default")
      (node (ref "RN2") (pin "5") (pinfunction "2_5") (pintype "passive"))
      (node (ref "U1") (pin "45") (pinfunction "PMODE0_45") (pintype "passive"))
    )
    (net (code "49") (name "Net-(U1-EXRES1)") (class "Default")
      (node (ref "R6") (pin "2") (pinfunction "2_2") (pintype "passive"))
      (node (ref "U1") (pin "10") (pinfunction "EXRES1_10") (pintype "passive"))
    )
    (net (code "50") (name "Net-(U1-RXN)") (class "Default")
      (node (ref "R37") (pin "2") (pinfunction "2_2") (pintype "passive"))
      (node (ref "U1") (pin "5") (pinfunction "RXN_5") (pintype "passive"))
    )
    (net (code "51") (name "Net-(U1-RXP)") (class "Default")
      (node (ref "R36") (pin "2") (pinfunction "2_2") (pintype "passive"))
      (node (ref "U1") (pin "6") (pinfunction "RXP_6") (pintype "passive"))
    )
    (net (code "52") (name "Net-(U1-TOCAP)") (class "Default")
      (node (ref "C16") (pin "1") (pinfunction "1_1") (pintype "passive"))
      (node (ref "U1") (pin "20") (pinfunction "TOCAP_20") (pintype "passive"))
    )
    (net (code "53") (name "Net-(U1-TXN)") (class "Default")
      (node (ref "R35") (pin "2") (pinfunction "2_2") (pintype "passive"))
      (node (ref "U1") (pin "1") (pinfunction "TXN_1") (pintype "passive"))
    )
    (net (code "54") (name "Net-(U1-TXP)") (class "Default")
      (node (ref "R34") (pin "2") (pinfunction "2_2") (pintype "passive"))
      (node (ref "U1") (pin "2") (pinfunction "TXP_2") (pintype "passive"))
    )
    (net (code "55") (name "Net-(U1-XO)") (class "Default")
      (node (ref "R17") (pin "2") (pinfunction "2_2") (pintype "passive"))
      (node (ref "R8") (pin "1") (pinfunction "1_1") (pintype "passive"))
      (node (ref "U1") (pin "31") (pinfunction "XO_31") (pintype "passive"))
    )
    (net (code "56") (name "RX_N") (class "Default")
      (node (ref "C13") (pin "1") (pinfunction "P$1_1") (pintype "passive"))
      (node (ref "R14") (pin "2") (pinfunction "2_2") (pintype "passive"))
      (node (ref "R37") (pin "1") (pinfunction "1_1") (pintype "passive"))
    )
    (net (code "57") (name "RX_P") (class "Default")
      (node (ref "C12") (pin "1") (pinfunction "P$1_1") (pintype "passive"))
      (node (ref "R13") (pin "2") (pinfunction "2_2") (pintype "passive"))
      (node (ref "R36") (pin "1") (pinfunction "1_1") (pintype "passive"))
    )
    (net (code "58") (name "SCLK") (class "Default")
      (node (ref "JP6") (pin "6") (pinfunction "6_6") (pintype "passive"))
      (node (ref "JP7") (pin "6") (pinfunction "6_6") (pintype "passive"))
      (node (ref "MS1") (pin "11") (pinfunction "GPIOSCK_11") (pintype "bidirectional"))
      (node (ref "MS2") (pin "11") (pinfunction "GPIOSCK_11") (pintype "bidirectional"))
      (node (ref "U1") (pin "33") (pinfunction "SCLK_33") (pintype "passive"))
    )
    (net (code "59") (name "SCSN") (class "Default")
      (node (ref "JP1") (pin "2") (pinfunction "2_2") (pintype "passive"))
      (node (ref "R21") (pin "1") (pinfunction "1_1") (pintype "passive"))
      (node (ref "U1") (pin "32") (pinfunction "SCS_N_32") (pintype "passive"))
    )
    (net (code "60") (name "TX_N") (class "Default")
      (node (ref "R10") (pin "1") (pinfunction "1_1") (pintype "passive"))
      (node (ref "R35") (pin "1") (pinfunction "1_1") (pintype "passive"))
      (node (ref "RJ45") (pin "R5") (pinfunction "TD-_R5") (pintype "bidirectional"))
    )
    (net (code "61") (name "TX_P") (class "Default")
      (node (ref "R11") (pin "1") (pinfunction "1_1") (pintype "passive"))
      (node (ref "R34") (pin "1") (pinfunction "1_1") (pintype "passive"))
      (node (ref "RJ45") (pin "R6") (pinfunction "TD+_R6") (pintype "bidirectional"))
    )
    (net (code "62") (name "V+") (class "Default")
      (node (ref "J3") (pin "2") (pinfunction "2_2") (pintype "passive"))
      (node (ref "RJ45") (pin "R9") (pinfunction "V+_R9") (pintype "bidirectional"))
    )
    (net (code "63") (name "V-") (class "Default")
      (node (ref "J3") (pin "1") (pinfunction "1_1") (pintype "passive"))
      (node (ref "RJ45") (pin "R10") (pinfunction "V-_R10") (pintype "bidirectional"))
    )
    (net (code "64") (name "VPOE") (class "Default")
      (node (ref "J1") (pin "1") (pinfunction "1_1") (pintype "passive"))
      (node (ref "JP8") (pin "3") (pinfunction "3_3") (pintype "passive"))
      (node (ref "JP9") (pin "3") (pinfunction "3_3") (pintype "passive"))
      (node (ref "MS1") (pin "26") (pinfunction "USB_26") (pintype "power_in"))
      (node (ref "MS2") (pin "26") (pinfunction "USB_26") (pintype "power_in"))
    )
    (net (code "65") (name "unconnected-(RJ45-NC-PadR7)") (class "Default")
      (node (ref "RJ45") (pin "R7") (pinfunction "NC_R7") (pintype "bidirectional"))
    )
    (net (code "66") (name "unconnected-(RJ45-NC-PadR8)") (class "Default")
      (node (ref "RJ45") (pin "R8") (pinfunction "NC_R8") (pintype "bidirectional"))
    )
    (net (code "67") (name "unconnected-(U1-DNC-Pad7)") (class "Default")
      (node (ref "U1") (pin "7") (pinfunction "DNC_7") (pintype "passive"))
    )
    (net (code "68") (name "unconnected-(U1-DUPLED-Pad26)") (class "Default")
      (node (ref "U1") (pin "26") (pinfunction "DUPLED_26") (pintype "passive"))
    )
    (net (code "69") (name "unconnected-(U1-NC-Pad12)") (class "Default")
      (node (ref "U1") (pin "12") (pinfunction "NC_12") (pintype "passive"))
    )
    (net (code "70") (name "unconnected-(U1-NC-Pad13)") (class "Default")
      (node (ref "U1") (pin "13") (pinfunction "NC_13") (pintype "passive"))
    )
    (net (code "71") (name "unconnected-(U1-NC-Pad46)") (class "Default")
      (node (ref "U1") (pin "46") (pinfunction "NC_46") (pintype "passive"))
    )
    (net (code "72") (name "unconnected-(U1-NC-Pad47)") (class "Default")
      (node (ref "U1") (pin "47") (pinfunction "NC_47") (pintype "passive"))
    )
    (net (code "73") (name "unconnected-(U1-SPDLED-Pad24)") (class "Default")
      (node (ref "U1") (pin "24") (pinfunction "SPDLED_24") (pintype "passive"))
    )
    (net (code "74") (name "unconnected-(U1-VBG-Pad18)") (class "Default")
      (node (ref "U1") (pin "18") (pinfunction "VBG_18") (pintype "passive"))
    )
    (net (code "75") (name "~{INTN}") (class "Default")
      (node (ref "JP2") (pin "2") (pinfunction "2_2") (pintype "passive"))
      (node (ref "R20") (pin "1") (pinfunction "1_1") (pintype "passive"))
      (node (ref "U1") (pin "36") (pinfunction "INT_N_36") (pintype "passive"))
    )
    (net (code "76") (name "~{RESET}") (class "Default")
      (node (ref "C10") (pin "2") (pinfunction "P$2_2") (pintype "passive"))
      (node (ref "D2") (pin "A") (pinfunction "A_A") (pintype "passive"))
      (node (ref "JP3") (pin "2") (pinfunction "2_2") (pintype "passive"))
      (node (ref "R2") (pin "1") (pinfunction "1_1") (pintype "passive"))
      (node (ref "U1") (pin "37") (pinfunction "RST_N_37") (pintype "passive"))
    )
  )
)
